# SCH_LED_driver_2023-04-18.net
KiCad netlist of a schematic drawn in EasyEDA
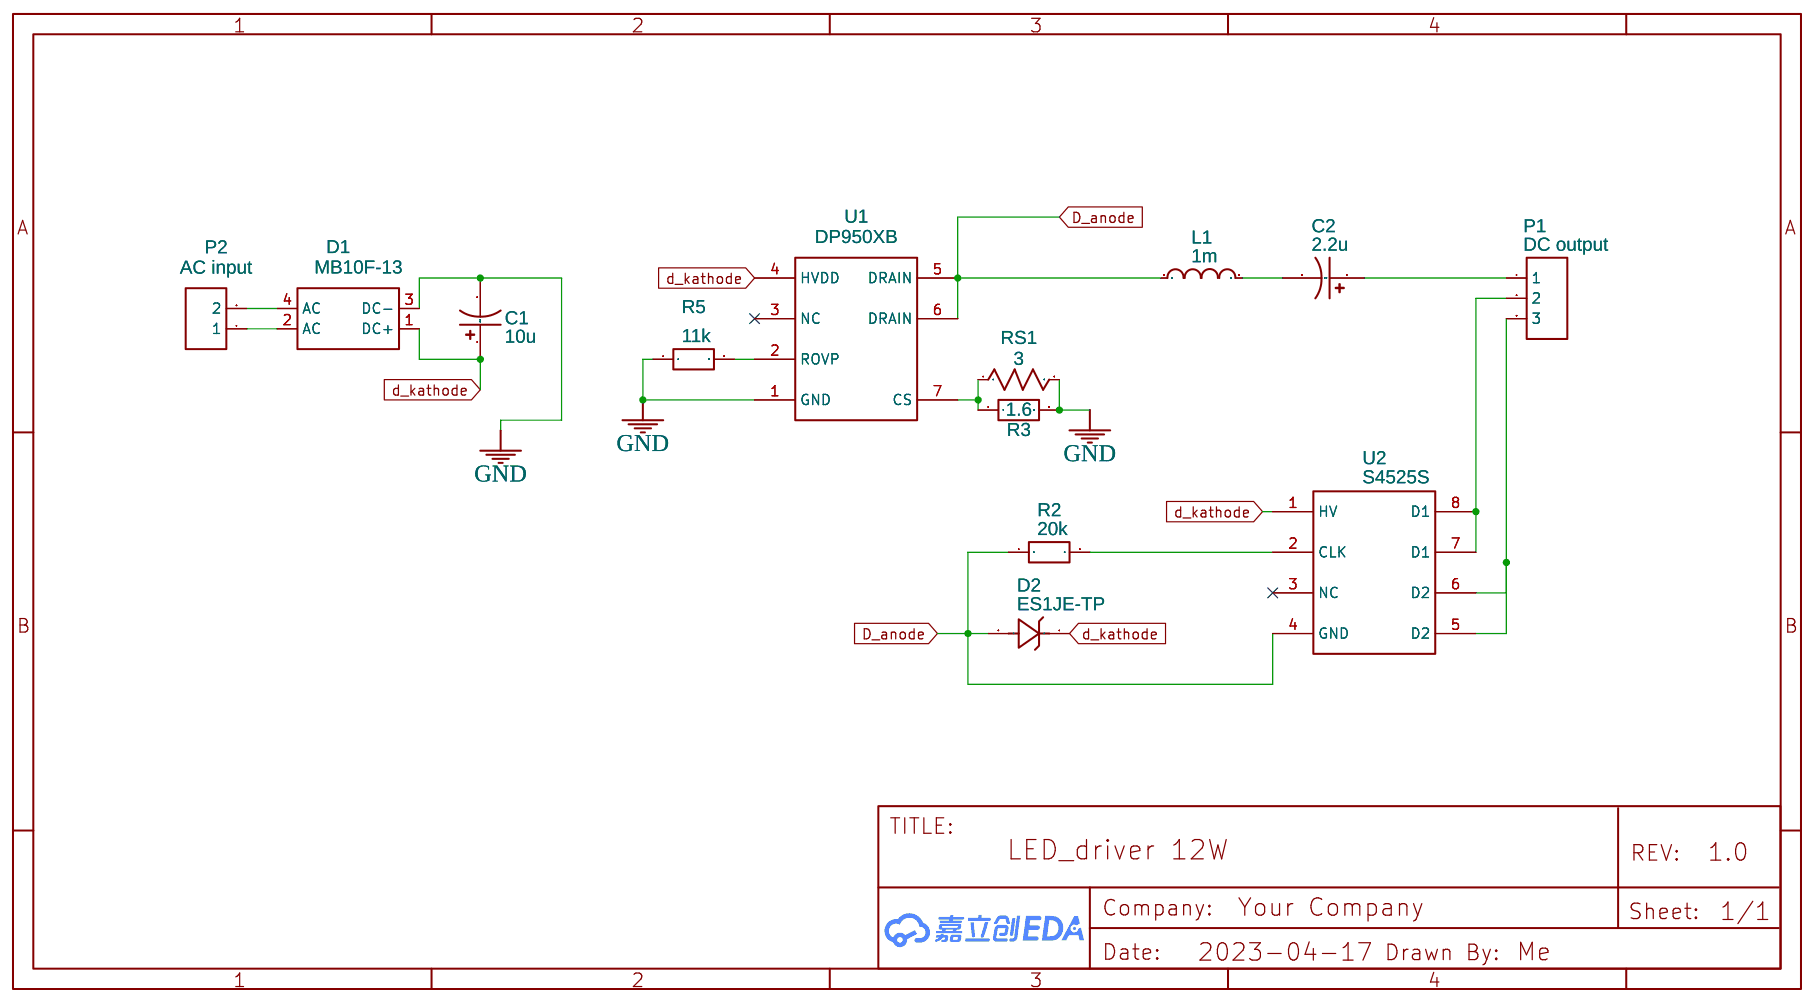
[diagram p0: schematic sheet]

(export (version "E")
  (design (tool "Eeschema 10.0.6"))
  (components
    (comp (ref "C1") (value "10u") (libsource (lib "") (part "C_Tan_SMD_A_US_1")))
    (comp (ref "C2") (value "2.2u") (libsource (lib "") (part "C_Tan_SMD_A_US")))
    (comp (ref "D1")
      (value "MB10F-13")
      (fields (field (name "BOM_Supplier Part") "C780855"))
      (libsource (lib "") (part "MB10F-13"))
    )
    (comp (ref "D2")
      (value "ES1JE-TP")
      (fields (field (name "BOM_Supplier Part") "C779061"))
      (libsource (lib "") (part "ES1JE-TP"))
    )
    (comp (ref "L1") (value "1m") (libsource (lib "") (part "L0603_US")))
    (comp (ref "P1") (value "DC output") (libsource (lib "") (part "CONN-TH_3P-P5.00")))
    (comp (ref "P2") (value "AC input") (libsource (lib "") (part "CONN-TH_2P-P5.00")))
    (comp (ref "R2") (value "20k") (libsource (lib "") (part "R_0603_EU")))
    (comp (ref "R3") (value "1.6") (libsource (lib "") (part "R_0603_EU")))
    (comp (ref "R5") (value "11k") (libsource (lib "") (part "R_0603_EU")))
    (comp (ref "RS1") (value "3") (libsource (lib "") (part "R_0603_US")))
    (comp (ref "U1") (value "DP950XB") (libsource (lib "") (part "DP950XB")))
    (comp (ref "U2")
      (value "S4525S")
      (fields (field (name "BOM_Supplier Part") "S4525S L3C54BX NCMJ14X"))
      (libsource (lib "") (part "S4525S"))
    )
  )
  (nets
    (net (code "1") (name "D_anode") (class "Default")
      (node (ref "D2") (pin "2") (pinfunction "A_2") (pintype "unspecified"))
      (node (ref "L1") (pin "1") (pinfunction "1_1") (pintype "unspecified"))
      (node (ref "R2") (pin "1") (pinfunction "1_1") (pintype "unspecified"))
      (node (ref "U1") (pin "5") (pinfunction "DRAIN_5") (pintype "unspecified"))
      (node (ref "U1") (pin "6") (pinfunction "DRAIN_6") (pintype "unspecified"))
      (node (ref "U2") (pin "4") (pinfunction "GND_4") (pintype "unspecified"))
    )
    (net (code "2") (name "GND") (class "Default")
      (node (ref "C1") (pin "2") (pinfunction "2_2") (pintype "unspecified"))
      (node (ref "D1") (pin "3") (pinfunction "DC-_3") (pintype "unspecified"))
      (node (ref "R3") (pin "2") (pinfunction "2_2") (pintype "unspecified"))
      (node (ref "R5") (pin "1") (pinfunction "1_1") (pintype "unspecified"))
      (node (ref "RS1") (pin "2") (pinfunction "2_2") (pintype "unspecified"))
      (node (ref "U1") (pin "1") (pinfunction "GND_1") (pintype "unspecified"))
    )
    (net (code "3") (name "Net-(C2-Pad1)") (class "Default")
      (node (ref "C2") (pin "1") (pinfunction "1_1") (pintype "unspecified"))
      (node (ref "P1") (pin "1") (pinfunction "1_1") (pintype "unspecified"))
    )
    (net (code "4") (name "Net-(C2-Pad2)") (class "Default")
      (node (ref "C2") (pin "2") (pinfunction "2_2") (pintype "unspecified"))
      (node (ref "L1") (pin "2") (pinfunction "2_2") (pintype "unspecified"))
    )
    (net (code "5") (name "Net-(D1-AC-Pad2)") (class "Default")
      (node (ref "D1") (pin "2") (pinfunction "AC_2") (pintype "unspecified"))
      (node (ref "P2") (pin "1") (pinfunction "1_1") (pintype "unspecified"))
    )
    (net (code "6") (name "Net-(D1-AC-Pad4)") (class "Default")
      (node (ref "D1") (pin "4") (pinfunction "AC_4") (pintype "unspecified"))
      (node (ref "P2") (pin "2") (pinfunction "2_2") (pintype "unspecified"))
    )
    (net (code "7") (name "Net-(P1-Pad2)") (class "Default")
      (node (ref "P1") (pin "2") (pinfunction "2_2") (pintype "unspecified"))
      (node (ref "U2") (pin "7") (pinfunction "D1_7") (pintype "unspecified"))
      (node (ref "U2") (pin "8") (pinfunction "D1_8") (pintype "unspecified"))
    )
    (net (code "8") (name "Net-(P1-Pad3)") (class "Default")
      (node (ref "P1") (pin "3") (pinfunction "3_3") (pintype "unspecified"))
      (node (ref "U2") (pin "5") (pinfunction "D2_5") (pintype "unspecified"))
      (node (ref "U2") (pin "6") (pinfunction "D2_6") (pintype "unspecified"))
    )
    (net (code "9") (name "Net-(U1-CS)") (class "Default")
      (node (ref "R3") (pin "1") (pinfunction "1_1") (pintype "unspecified"))
      (node (ref "RS1") (pin "1") (pinfunction "1_1") (pintype "unspecified"))
      (node (ref "U1") (pin "7") (pinfunction "CS_7") (pintype "unspecified"))
    )
    (net (code "10") (name "Net-(U1-ROVP)") (class "Default")
      (node (ref "R5") (pin "2") (pinfunction "2_2") (pintype "unspecified"))
      (node (ref "U1") (pin "2") (pinfunction "ROVP_2") (pintype "unspecified"))
    )
    (net (code "11") (name "Net-(U2-CLK)") (class "Default")
      (node (ref "R2") (pin "2") (pinfunction "2_2") (pintype "unspecified"))
      (node (ref "U2") (pin "2") (pinfunction "CLK_2") (pintype "unspecified"))
    )
    (net (code "12") (name "d_kathode") (class "Default")
      (node (ref "C1") (pin "1") (pinfunction "1_1") (pintype "unspecified"))
      (node (ref "D1") (pin "1") (pinfunction "DC+_1") (pintype "unspecified"))
      (node (ref "D2") (pin "1") (pinfunction "K_1") (pintype "unspecified"))
      (node (ref "U1") (pin "4") (pinfunction "HVDD_4") (pintype "unspecified"))
      (node (ref "U2") (pin "1") (pinfunction "HV_1") (pintype "unspecified"))
    )
    (net (code "13") (name "unconnected-(U1-NC-Pad3)") (class "Default")
      (node (ref "U1") (pin "3") (pinfunction "NC_3") (pintype "unspecified+no_connect"))
    )
    (net (code "14") (name "unconnected-(U2-NC-Pad3)") (class "Default")
      (node (ref "U2") (pin "3") (pinfunction "NC_3") (pintype "unspecified+no_connect"))
    )
  )
)
